# A601X.net
KiCad netlist of a schematic drawn in EAGLE
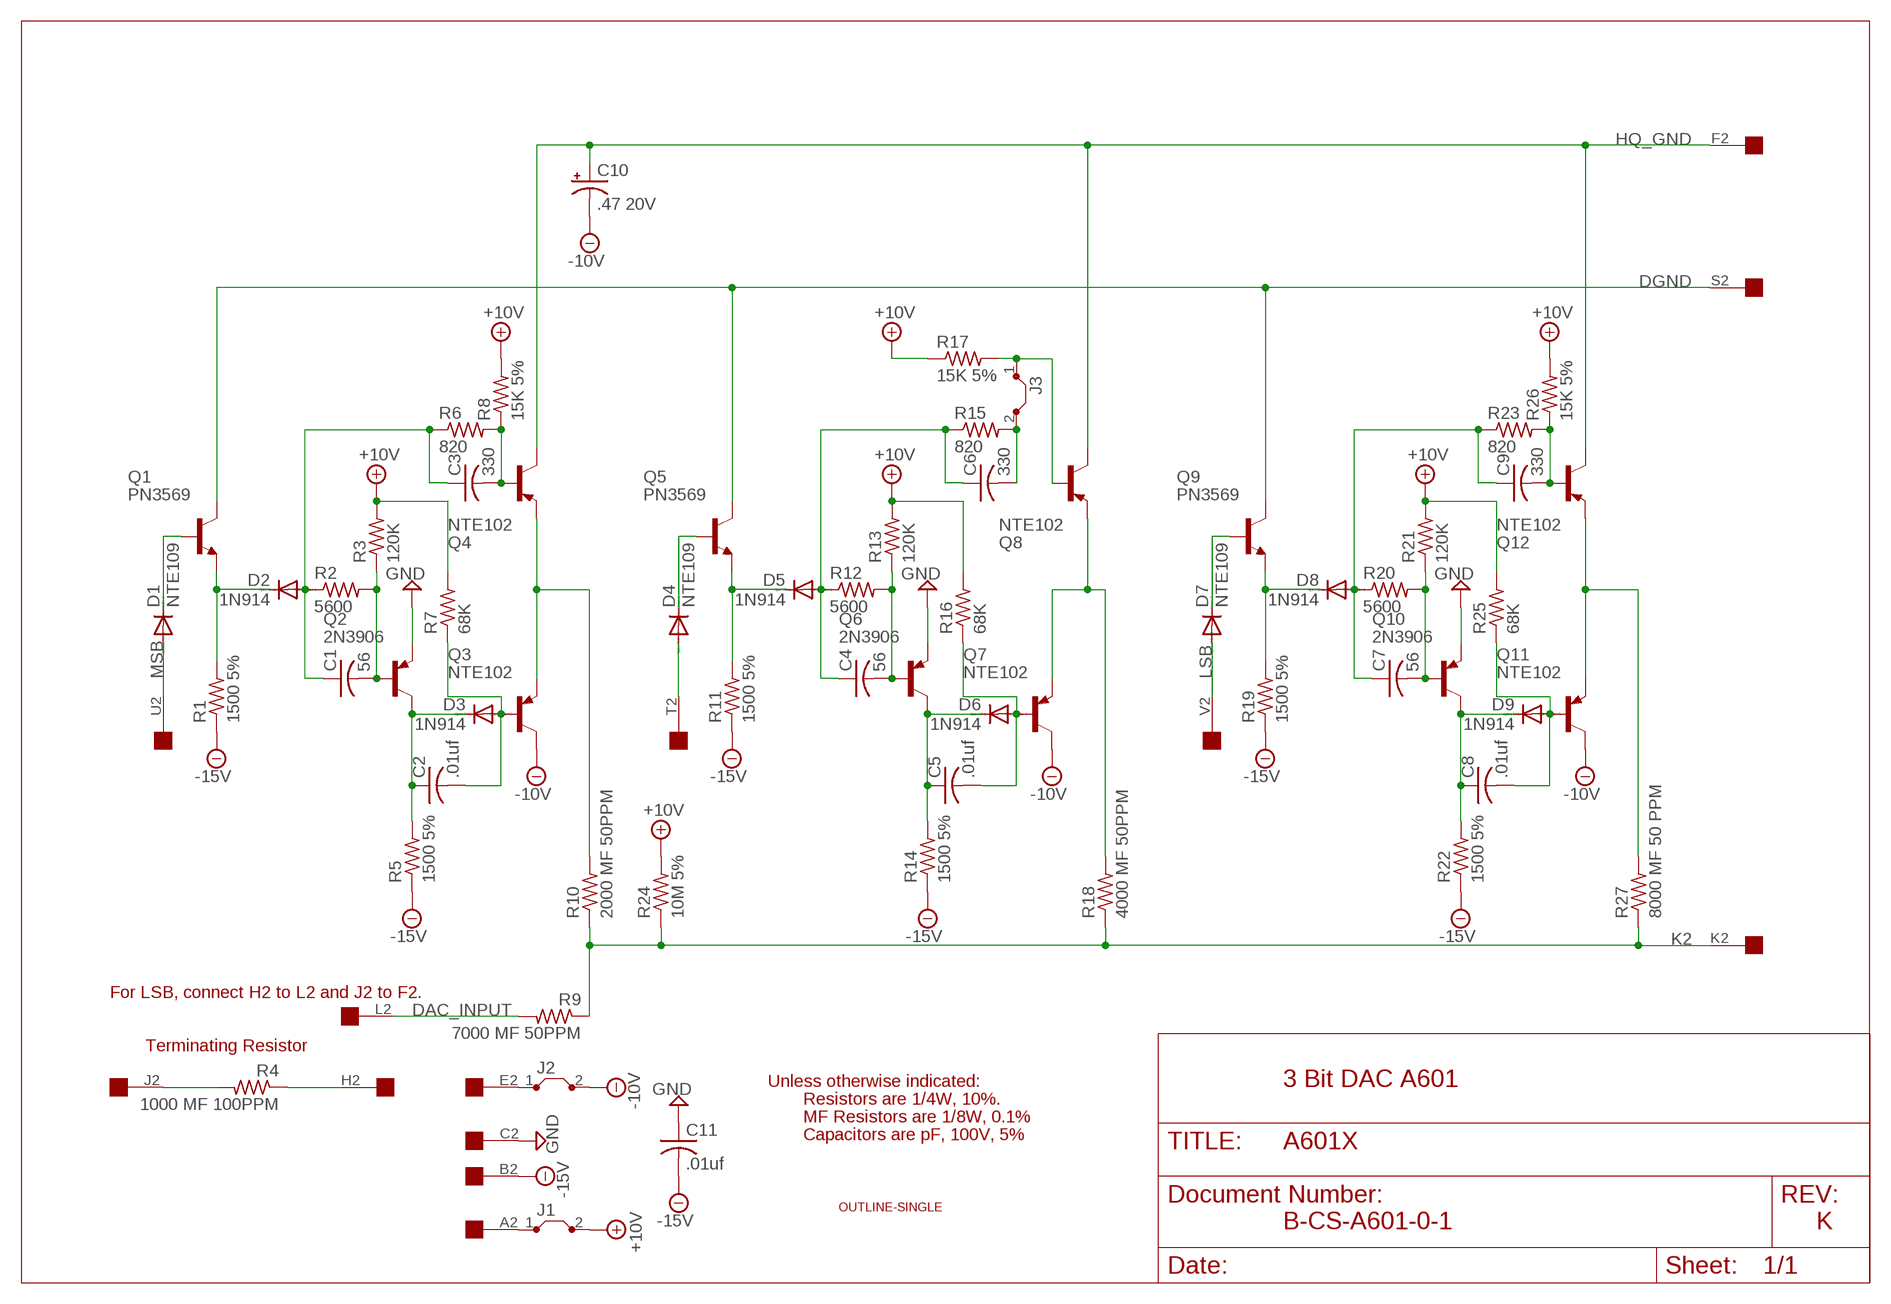
[diagram p0: schematic, sheet 1]

(export (version "E")
  (design (tool "Eeschema 10.0.6"))
  (components
    (comp (ref "C1")
      (value "56")
      (footprint "eagle-import:C075-032X103")
      (libsource (lib "eagle-import") (part "C-US075-032X103"))
    )
    (comp (ref "C2")
      (value ".01uf")
      (footprint "eagle-import:C050-025X075")
      (libsource (lib "eagle-import") (part "C-US050-025X075"))
    )
    (comp (ref "C3")
      (value "330")
      (footprint "eagle-import:C075-032X103")
      (libsource (lib "eagle-import") (part "C-US075-032X103"))
    )
    (comp (ref "C4")
      (value "56")
      (footprint "eagle-import:C075-032X103")
      (libsource (lib "eagle-import") (part "C-US075-032X103"))
    )
    (comp (ref "C5")
      (value ".01uf")
      (footprint "eagle-import:C050-025X075")
      (libsource (lib "eagle-import") (part "C-US050-025X075"))
    )
    (comp (ref "C6")
      (value "330")
      (footprint "eagle-import:C075-032X103")
      (libsource (lib "eagle-import") (part "C-US075-032X103"))
    )
    (comp (ref "C7")
      (value "56")
      (footprint "eagle-import:C075-032X103")
      (libsource (lib "eagle-import") (part "C-US075-032X103"))
    )
    (comp (ref "C8")
      (value ".01uf")
      (footprint "eagle-import:C050-025X075")
      (libsource (lib "eagle-import") (part "C-US050-025X075"))
    )
    (comp (ref "C9")
      (value "330")
      (footprint "eagle-import:C075-032X103")
      (libsource (lib "eagle-import") (part "C-US075-032X103"))
    )
    (comp (ref "C10")
      (value ".47 20V")
      (footprint "eagle-import:E22-6")
      (libsource (lib "eagle-import") (part "CPOL-USE22-6AXIAL"))
    )
    (comp (ref "C11")
      (value ".01uf")
      (footprint "eagle-import:C050-025X075")
      (libsource (lib "eagle-import") (part "C-US050-025X075"))
    )
    (comp (ref "D1")
      (value "NTE109")
      (footprint "eagle-import:DO35-10")
      (libsource (lib "eagle-import") (part "1N4148DO35-10"))
    )
    (comp (ref "D2")
      (value "1N914")
      (footprint "eagle-import:DO35-10")
      (libsource (lib "eagle-import") (part "1N4148DO35-10"))
    )
    (comp (ref "D3")
      (value "1N914")
      (footprint "eagle-import:DO35-10")
      (libsource (lib "eagle-import") (part "1N4148DO35-10"))
    )
    (comp (ref "D4")
      (value "NTE109")
      (footprint "eagle-import:DO35-10")
      (libsource (lib "eagle-import") (part "1N4148DO35-10"))
    )
    (comp (ref "D5")
      (value "1N914")
      (footprint "eagle-import:DO35-10")
      (libsource (lib "eagle-import") (part "1N4148DO35-10"))
    )
    (comp (ref "D6")
      (value "1N914")
      (footprint "eagle-import:DO35-10")
      (libsource (lib "eagle-import") (part "1N4148DO35-10"))
    )
    (comp (ref "D7")
      (value "NTE109")
      (footprint "eagle-import:DO35-10")
      (libsource (lib "eagle-import") (part "1N4148DO35-10"))
    )
    (comp (ref "D8")
      (value "1N914")
      (footprint "eagle-import:DO35-10")
      (libsource (lib "eagle-import") (part "1N4148DO35-10"))
    )
    (comp (ref "D9")
      (value "1N914")
      (footprint "eagle-import:DO35-10")
      (libsource (lib "eagle-import") (part "1N4148DO35-10"))
    )
    (comp (ref "J1")
      (value "J10MM")
      (footprint "eagle-import:10")
      (libsource (lib "eagle-import") (part "J10MM"))
    )
    (comp (ref "J2")
      (value "J10MM")
      (footprint "eagle-import:10")
      (libsource (lib "eagle-import") (part "J10MM"))
    )
    (comp (ref "J3")
      (value "J10MM")
      (footprint "eagle-import:10")
      (libsource (lib "eagle-import") (part "J10MM"))
    )
    (comp (ref "Q1")
      (value "PN3569")
      (footprint "eagle-import:TO39")
      (libsource (lib "eagle-import") (part "-NPN-TO39-EBC2N1613"))
    )
    (comp (ref "Q2")
      (value "2N3906")
      (footprint "eagle-import:TO39")
      (libsource (lib "eagle-import") (part "2N2904A"))
    )
    (comp (ref "Q3")
      (value "NTE102")
      (footprint "eagle-import:TO39")
      (libsource (lib "eagle-import") (part "2N2904A"))
    )
    (comp (ref "Q4")
      (value "NTE102")
      (footprint "eagle-import:TO39")
      (libsource (lib "eagle-import") (part "2N2904A"))
    )
    (comp (ref "Q5")
      (value "PN3569")
      (footprint "eagle-import:TO39")
      (libsource (lib "eagle-import") (part "-NPN-TO39-EBC2N1613"))
    )
    (comp (ref "Q6")
      (value "2N3906")
      (footprint "eagle-import:TO39")
      (libsource (lib "eagle-import") (part "2N2904A"))
    )
    (comp (ref "Q7")
      (value "NTE102")
      (footprint "eagle-import:TO39")
      (libsource (lib "eagle-import") (part "2N2904A"))
    )
    (comp (ref "Q8")
      (value "NTE102")
      (footprint "eagle-import:TO39")
      (libsource (lib "eagle-import") (part "2N2904A"))
    )
    (comp (ref "Q9")
      (value "PN3569")
      (footprint "eagle-import:TO39")
      (libsource (lib "eagle-import") (part "-NPN-TO39-EBC2N1613"))
    )
    (comp (ref "Q10")
      (value "2N3906")
      (footprint "eagle-import:TO39")
      (libsource (lib "eagle-import") (part "2N2904A"))
    )
    (comp (ref "Q11")
      (value "NTE102")
      (footprint "eagle-import:TO39")
      (libsource (lib "eagle-import") (part "2N2904A"))
    )
    (comp (ref "Q12")
      (value "NTE102")
      (footprint "eagle-import:TO39")
      (libsource (lib "eagle-import") (part "2N2904A"))
    )
    (comp (ref "R1")
      (value "1500 5%")
      (footprint "eagle-import:0207_10")
      (libsource (lib "eagle-import") (part "R-US_0207/10"))
    )
    (comp (ref "R2")
      (value "5600")
      (footprint "eagle-import:0207_10")
      (libsource (lib "eagle-import") (part "R-US_0207/10"))
    )
    (comp (ref "R3")
      (value "120K")
      (footprint "eagle-import:0207_10")
      (libsource (lib "eagle-import") (part "R-US_0207/10"))
    )
    (comp (ref "R4")
      (value "1000 MF 100PPM")
      (footprint "eagle-import:0309_12")
      (libsource (lib "eagle-import") (part "R-US_0309/12"))
    )
    (comp (ref "R5")
      (value "1500 5%")
      (footprint "eagle-import:0207_10")
      (libsource (lib "eagle-import") (part "R-US_0207/10"))
    )
    (comp (ref "R6")
      (value "820")
      (footprint "eagle-import:0207_10")
      (libsource (lib "eagle-import") (part "R-US_0207/10"))
    )
    (comp (ref "R7")
      (value "68K")
      (footprint "eagle-import:0207_10")
      (libsource (lib "eagle-import") (part "R-US_0207/10"))
    )
    (comp (ref "R8")
      (value "15K 5%")
      (footprint "eagle-import:0207_10")
      (libsource (lib "eagle-import") (part "R-US_0207/10"))
    )
    (comp (ref "R9")
      (value "7000 MF 50PPM")
      (footprint "eagle-import:0309_12")
      (libsource (lib "eagle-import") (part "R-US_0309/12"))
    )
    (comp (ref "R10")
      (value "2000 MF 50PPM")
      (footprint "eagle-import:0309_12")
      (libsource (lib "eagle-import") (part "R-US_0309/12"))
    )
    (comp (ref "R11")
      (value "1500 5%")
      (footprint "eagle-import:0207_10")
      (libsource (lib "eagle-import") (part "R-US_0207/10"))
    )
    (comp (ref "R12")
      (value "5600")
      (footprint "eagle-import:0207_10")
      (libsource (lib "eagle-import") (part "R-US_0207/10"))
    )
    (comp (ref "R13")
      (value "120K")
      (footprint "eagle-import:0207_10")
      (libsource (lib "eagle-import") (part "R-US_0207/10"))
    )
    (comp (ref "R14")
      (value "1500 5%")
      (footprint "eagle-import:0207_10")
      (libsource (lib "eagle-import") (part "R-US_0207/10"))
    )
    (comp (ref "R15")
      (value "820")
      (footprint "eagle-import:0207_10")
      (libsource (lib "eagle-import") (part "R-US_0207/10"))
    )
    (comp (ref "R16")
      (value "68K")
      (footprint "eagle-import:0207_10")
      (libsource (lib "eagle-import") (part "R-US_0207/10"))
    )
    (comp (ref "R17")
      (value "15K 5%")
      (footprint "eagle-import:0207_10")
      (libsource (lib "eagle-import") (part "R-US_0207/10"))
    )
    (comp (ref "R18")
      (value "4000 MF 50PPM")
      (footprint "eagle-import:0309_12")
      (libsource (lib "eagle-import") (part "R-US_0309/12"))
    )
    (comp (ref "R19")
      (value "1500 5%")
      (footprint "eagle-import:0207_10")
      (libsource (lib "eagle-import") (part "R-US_0207/10"))
    )
    (comp (ref "R20")
      (value "5600")
      (footprint "eagle-import:0207_10")
      (libsource (lib "eagle-import") (part "R-US_0207/10"))
    )
    (comp (ref "R21")
      (value "120K")
      (footprint "eagle-import:0207_10")
      (libsource (lib "eagle-import") (part "R-US_0207/10"))
    )
    (comp (ref "R22")
      (value "1500 5%")
      (footprint "eagle-import:0207_10")
      (libsource (lib "eagle-import") (part "R-US_0207/10"))
    )
    (comp (ref "R23")
      (value "820")
      (footprint "eagle-import:0207_10")
      (libsource (lib "eagle-import") (part "R-US_0207/10"))
    )
    (comp (ref "R24")
      (value "10M 5%")
      (footprint "eagle-import:0207_10")
      (libsource (lib "eagle-import") (part "R-US_0207/10"))
    )
    (comp (ref "R25")
      (value "68K")
      (footprint "eagle-import:0207_10")
      (libsource (lib "eagle-import") (part "R-US_0207/10"))
    )
    (comp (ref "R26")
      (value "15K 5%")
      (footprint "eagle-import:0207_10")
      (libsource (lib "eagle-import") (part "R-US_0207/10"))
    )
    (comp (ref "R27")
      (value "8000 MF 50 PPM")
      (footprint "eagle-import:0309_12")
      (libsource (lib "eagle-import") (part "R-US_0309/12"))
    )
    (comp (ref "U$1")
      (value "OUTLINE-SINGLE")
      (footprint "eagle-import:SINGLE")
      (libsource (lib "eagle-import") (part "OUTLINE-SINGLE"))
    )
    (comp (ref "U$3")
      (value "EDGE-1")
      (footprint "eagle-import:EDGE-CON1")
      (libsource (lib "eagle-import") (part "EDGE-1"))
    )
  )
  (nets
    (net (code "1") (name "+10V") (class "Default")
      (node (ref "J1") (pin "2") (pinfunction "2_2") (pintype "passive"))
      (node (ref "R13") (pin "2") (pinfunction "2_2") (pintype "passive"))
      (node (ref "R16") (pin "2") (pinfunction "2_2") (pintype "passive"))
      (node (ref "R17") (pin "1") (pinfunction "1_1") (pintype "passive"))
      (node (ref "R21") (pin "2") (pinfunction "2_2") (pintype "passive"))
      (node (ref "R24") (pin "2") (pinfunction "2_2") (pintype "passive"))
      (node (ref "R25") (pin "2") (pinfunction "2_2") (pintype "passive"))
      (node (ref "R26") (pin "2") (pinfunction "2_2") (pintype "passive"))
      (node (ref "R3") (pin "2") (pinfunction "2_2") (pintype "passive"))
      (node (ref "R7") (pin "2") (pinfunction "2_2") (pintype "passive"))
      (node (ref "R8") (pin "2") (pinfunction "2_2") (pintype "passive"))
    )
    (net (code "2") (name "-10V") (class "Default")
      (node (ref "C10") (pin "-") (pinfunction "-_-") (pintype "passive"))
      (node (ref "J2") (pin "2") (pinfunction "2_2") (pintype "passive"))
      (node (ref "Q11") (pin "3") (pinfunction "C_3") (pintype "passive"))
      (node (ref "Q3") (pin "3") (pinfunction "C_3") (pintype "passive"))
      (node (ref "Q7") (pin "3") (pinfunction "C_3") (pintype "passive"))
    )
    (net (code "3") (name "-15V") (class "Default")
      (node (ref "C11") (pin "2") (pinfunction "2_2") (pintype "passive"))
      (node (ref "R1") (pin "1") (pinfunction "1_1") (pintype "passive"))
      (node (ref "R11") (pin "1") (pinfunction "1_1") (pintype "passive"))
      (node (ref "R14") (pin "1") (pinfunction "1_1") (pintype "passive"))
      (node (ref "R19") (pin "1") (pinfunction "1_1") (pintype "passive"))
      (node (ref "R22") (pin "1") (pinfunction "1_1") (pintype "passive"))
      (node (ref "R5") (pin "1") (pinfunction "1_1") (pintype "passive"))
      (node (ref "U$3") (pin "B2") (pinfunction "1_B2") (pintype "bidirectional"))
    )
    (net (code "4") (name "/DAC_INPUT") (class "Default")
      (node (ref "R9") (pin "2") (pinfunction "2_2") (pintype "passive"))
      (node (ref "U$3") (pin "L2") (pinfunction "1_L2") (pintype "bidirectional"))
    )
    (net (code "5") (name "/DGND") (class "Default")
      (node (ref "Q1") (pin "3") (pinfunction "C_3") (pintype "passive"))
      (node (ref "Q5") (pin "3") (pinfunction "C_3") (pintype "passive"))
      (node (ref "Q9") (pin "3") (pinfunction "C_3") (pintype "passive"))
      (node (ref "U$3") (pin "S2") (pinfunction "1_S2") (pintype "bidirectional"))
    )
    (net (code "6") (name "/HQ_GND") (class "Default")
      (node (ref "C10") (pin "+") (pinfunction "+_+") (pintype "passive"))
      (node (ref "Q12") (pin "3") (pinfunction "C_3") (pintype "passive"))
      (node (ref "Q4") (pin "3") (pinfunction "C_3") (pintype "passive"))
      (node (ref "Q8") (pin "3") (pinfunction "C_3") (pintype "passive"))
      (node (ref "U$3") (pin "F2") (pinfunction "1_F2") (pintype "bidirectional"))
    )
    (net (code "7") (name "/K2") (class "Default")
      (node (ref "R10") (pin "1") (pinfunction "1_1") (pintype "passive"))
      (node (ref "R18") (pin "1") (pinfunction "1_1") (pintype "passive"))
      (node (ref "R24") (pin "1") (pinfunction "1_1") (pintype "passive"))
      (node (ref "R27") (pin "1") (pinfunction "1_1") (pintype "passive"))
      (node (ref "R9") (pin "1") (pinfunction "1_1") (pintype "passive"))
      (node (ref "U$3") (pin "K2") (pinfunction "1_K2") (pintype "bidirectional"))
    )
    (net (code "8") (name "/LSB") (class "Default")
      (node (ref "D7") (pin "A") (pinfunction "A_A") (pintype "passive"))
      (node (ref "U$3") (pin "V2") (pinfunction "1_V2") (pintype "bidirectional"))
    )
    (net (code "9") (name "/MSB") (class "Default")
      (node (ref "D1") (pin "A") (pinfunction "A_A") (pintype "passive"))
      (node (ref "U$3") (pin "U2") (pinfunction "1_U2") (pintype "bidirectional"))
    )
    (net (code "10") (name "GND") (class "Default")
      (node (ref "C11") (pin "1") (pinfunction "1_1") (pintype "passive"))
      (node (ref "Q10") (pin "1") (pinfunction "E_1") (pintype "passive"))
      (node (ref "Q2") (pin "1") (pinfunction "E_1") (pintype "passive"))
      (node (ref "Q6") (pin "1") (pinfunction "E_1") (pintype "passive"))
      (node (ref "U$3") (pin "C2") (pinfunction "1_C2") (pintype "bidirectional"))
    )
    (net (code "11") (name "Net-(C1-Pad1)") (class "Default")
      (node (ref "C1") (pin "1") (pinfunction "1_1") (pintype "passive"))
      (node (ref "C3") (pin "1") (pinfunction "1_1") (pintype "passive"))
      (node (ref "D2") (pin "A") (pinfunction "A_A") (pintype "passive"))
      (node (ref "R2") (pin "1") (pinfunction "1_1") (pintype "passive"))
      (node (ref "R6") (pin "1") (pinfunction "1_1") (pintype "passive"))
    )
    (net (code "12") (name "Net-(C4-Pad1)") (class "Default")
      (node (ref "C4") (pin "1") (pinfunction "1_1") (pintype "passive"))
      (node (ref "C6") (pin "1") (pinfunction "1_1") (pintype "passive"))
      (node (ref "D5") (pin "A") (pinfunction "A_A") (pintype "passive"))
      (node (ref "R12") (pin "1") (pinfunction "1_1") (pintype "passive"))
      (node (ref "R15") (pin "1") (pinfunction "1_1") (pintype "passive"))
    )
    (net (code "13") (name "Net-(C6-Pad2)") (class "Default")
      (node (ref "C6") (pin "2") (pinfunction "2_2") (pintype "passive"))
      (node (ref "J3") (pin "2") (pinfunction "2_2") (pintype "passive"))
      (node (ref "R15") (pin "2") (pinfunction "2_2") (pintype "passive"))
    )
    (net (code "14") (name "Net-(C7-Pad1)") (class "Default")
      (node (ref "C7") (pin "1") (pinfunction "1_1") (pintype "passive"))
      (node (ref "C9") (pin "1") (pinfunction "1_1") (pintype "passive"))
      (node (ref "D8") (pin "A") (pinfunction "A_A") (pintype "passive"))
      (node (ref "R20") (pin "1") (pinfunction "1_1") (pintype "passive"))
      (node (ref "R23") (pin "1") (pinfunction "1_1") (pintype "passive"))
    )
    (net (code "15") (name "Net-(Q1-B)") (class "Default")
      (node (ref "D1") (pin "C") (pinfunction "C_C") (pintype "passive"))
      (node (ref "Q1") (pin "2") (pinfunction "B_2") (pintype "passive"))
    )
    (net (code "16") (name "Net-(Q1-E)") (class "Default")
      (node (ref "D2") (pin "C") (pinfunction "C_C") (pintype "passive"))
      (node (ref "Q1") (pin "1") (pinfunction "E_1") (pintype "passive"))
      (node (ref "R1") (pin "2") (pinfunction "2_2") (pintype "passive"))
    )
    (net (code "17") (name "Net-(Q2-B)") (class "Default")
      (node (ref "C1") (pin "2") (pinfunction "2_2") (pintype "passive"))
      (node (ref "Q2") (pin "2") (pinfunction "B_2") (pintype "passive"))
      (node (ref "R2") (pin "2") (pinfunction "2_2") (pintype "passive"))
      (node (ref "R3") (pin "1") (pinfunction "1_1") (pintype "passive"))
    )
    (net (code "18") (name "Net-(Q2-C)") (class "Default")
      (node (ref "C2") (pin "1") (pinfunction "1_1") (pintype "passive"))
      (node (ref "D3") (pin "C") (pinfunction "C_C") (pintype "passive"))
      (node (ref "Q2") (pin "3") (pinfunction "C_3") (pintype "passive"))
      (node (ref "R5") (pin "2") (pinfunction "2_2") (pintype "passive"))
    )
    (net (code "19") (name "Net-(Q3-B)") (class "Default")
      (node (ref "C2") (pin "2") (pinfunction "2_2") (pintype "passive"))
      (node (ref "D3") (pin "A") (pinfunction "A_A") (pintype "passive"))
      (node (ref "Q3") (pin "2") (pinfunction "B_2") (pintype "passive"))
      (node (ref "R7") (pin "1") (pinfunction "1_1") (pintype "passive"))
    )
    (net (code "20") (name "Net-(Q3-E)") (class "Default")
      (node (ref "Q3") (pin "1") (pinfunction "E_1") (pintype "passive"))
      (node (ref "Q4") (pin "1") (pinfunction "E_1") (pintype "passive"))
      (node (ref "R10") (pin "2") (pinfunction "2_2") (pintype "passive"))
    )
    (net (code "21") (name "Net-(Q4-B)") (class "Default")
      (node (ref "C3") (pin "2") (pinfunction "2_2") (pintype "passive"))
      (node (ref "Q4") (pin "2") (pinfunction "B_2") (pintype "passive"))
      (node (ref "R6") (pin "2") (pinfunction "2_2") (pintype "passive"))
      (node (ref "R8") (pin "1") (pinfunction "1_1") (pintype "passive"))
    )
    (net (code "22") (name "Net-(Q5-B)") (class "Default")
      (node (ref "D4") (pin "C") (pinfunction "C_C") (pintype "passive"))
      (node (ref "Q5") (pin "2") (pinfunction "B_2") (pintype "passive"))
    )
    (net (code "23") (name "Net-(Q5-E)") (class "Default")
      (node (ref "D5") (pin "C") (pinfunction "C_C") (pintype "passive"))
      (node (ref "Q5") (pin "1") (pinfunction "E_1") (pintype "passive"))
      (node (ref "R11") (pin "2") (pinfunction "2_2") (pintype "passive"))
    )
    (net (code "24") (name "Net-(Q6-B)") (class "Default")
      (node (ref "C4") (pin "2") (pinfunction "2_2") (pintype "passive"))
      (node (ref "Q6") (pin "2") (pinfunction "B_2") (pintype "passive"))
      (node (ref "R12") (pin "2") (pinfunction "2_2") (pintype "passive"))
      (node (ref "R13") (pin "1") (pinfunction "1_1") (pintype "passive"))
    )
    (net (code "25") (name "Net-(Q6-C)") (class "Default")
      (node (ref "C5") (pin "1") (pinfunction "1_1") (pintype "passive"))
      (node (ref "D6") (pin "C") (pinfunction "C_C") (pintype "passive"))
      (node (ref "Q6") (pin "3") (pinfunction "C_3") (pintype "passive"))
      (node (ref "R14") (pin "2") (pinfunction "2_2") (pintype "passive"))
    )
    (net (code "26") (name "Net-(Q7-B)") (class "Default")
      (node (ref "C5") (pin "2") (pinfunction "2_2") (pintype "passive"))
      (node (ref "D6") (pin "A") (pinfunction "A_A") (pintype "passive"))
      (node (ref "Q7") (pin "2") (pinfunction "B_2") (pintype "passive"))
      (node (ref "R16") (pin "1") (pinfunction "1_1") (pintype "passive"))
    )
    (net (code "27") (name "Net-(Q7-E)") (class "Default")
      (node (ref "Q7") (pin "1") (pinfunction "E_1") (pintype "passive"))
      (node (ref "Q8") (pin "1") (pinfunction "E_1") (pintype "passive"))
      (node (ref "R18") (pin "2") (pinfunction "2_2") (pintype "passive"))
    )
    (net (code "28") (name "Net-(Q8-B)") (class "Default")
      (node (ref "J3") (pin "1") (pinfunction "1_1") (pintype "passive"))
      (node (ref "Q8") (pin "2") (pinfunction "B_2") (pintype "passive"))
      (node (ref "R17") (pin "2") (pinfunction "2_2") (pintype "passive"))
    )
    (net (code "29") (name "Net-(Q9-B)") (class "Default")
      (node (ref "D7") (pin "C") (pinfunction "C_C") (pintype "passive"))
      (node (ref "Q9") (pin "2") (pinfunction "B_2") (pintype "passive"))
    )
    (net (code "30") (name "Net-(Q9-E)") (class "Default")
      (node (ref "D8") (pin "C") (pinfunction "C_C") (pintype "passive"))
      (node (ref "Q9") (pin "1") (pinfunction "E_1") (pintype "passive"))
      (node (ref "R19") (pin "2") (pinfunction "2_2") (pintype "passive"))
    )
    (net (code "31") (name "Net-(Q10-B)") (class "Default")
      (node (ref "C7") (pin "2") (pinfunction "2_2") (pintype "passive"))
      (node (ref "Q10") (pin "2") (pinfunction "B_2") (pintype "passive"))
      (node (ref "R20") (pin "2") (pinfunction "2_2") (pintype "passive"))
      (node (ref "R21") (pin "1") (pinfunction "1_1") (pintype "passive"))
    )
    (net (code "32") (name "Net-(Q10-C)") (class "Default")
      (node (ref "C8") (pin "1") (pinfunction "1_1") (pintype "passive"))
      (node (ref "D9") (pin "C") (pinfunction "C_C") (pintype "passive"))
      (node (ref "Q10") (pin "3") (pinfunction "C_3") (pintype "passive"))
      (node (ref "R22") (pin "2") (pinfunction "2_2") (pintype "passive"))
    )
    (net (code "33") (name "Net-(Q11-B)") (class "Default")
      (node (ref "C8") (pin "2") (pinfunction "2_2") (pintype "passive"))
      (node (ref "D9") (pin "A") (pinfunction "A_A") (pintype "passive"))
      (node (ref "Q11") (pin "2") (pinfunction "B_2") (pintype "passive"))
      (node (ref "R25") (pin "1") (pinfunction "1_1") (pintype "passive"))
    )
    (net (code "34") (name "Net-(Q11-E)") (class "Default")
      (node (ref "Q11") (pin "1") (pinfunction "E_1") (pintype "passive"))
      (node (ref "Q12") (pin "1") (pinfunction "E_1") (pintype "passive"))
      (node (ref "R27") (pin "2") (pinfunction "2_2") (pintype "passive"))
    )
    (net (code "35") (name "Net-(Q12-B)") (class "Default")
      (node (ref "C9") (pin "2") (pinfunction "2_2") (pintype "passive"))
      (node (ref "Q12") (pin "2") (pinfunction "B_2") (pintype "passive"))
      (node (ref "R23") (pin "2") (pinfunction "2_2") (pintype "passive"))
      (node (ref "R26") (pin "1") (pinfunction "1_1") (pintype "passive"))
    )
    (net (code "36") (name "Net-(U$3A-1)") (class "Default")
      (node (ref "J1") (pin "1") (pinfunction "1_1") (pintype "passive"))
      (node (ref "U$3") (pin "A2") (pinfunction "1_A2") (pintype "bidirectional"))
    )
    (net (code "37") (name "Net-(U$3E-1)") (class "Default")
      (node (ref "J2") (pin "1") (pinfunction "1_1") (pintype "passive"))
      (node (ref "U$3") (pin "E2") (pinfunction "1_E2") (pintype "bidirectional"))
    )
    (net (code "38") (name "Net-(U$3G-1)") (class "Default")
      (node (ref "R4") (pin "1") (pinfunction "1_1") (pintype "passive"))
      (node (ref "U$3") (pin "H2") (pinfunction "1_H2") (pintype "bidirectional"))
    )
    (net (code "39") (name "Net-(U$3H-1)") (class "Default")
      (node (ref "R4") (pin "2") (pinfunction "2_2") (pintype "passive"))
      (node (ref "U$3") (pin "J2") (pinfunction "1_J2") (pintype "bidirectional"))
    )
    (net (code "40") (name "Net-(U$3P-1)") (class "Default")
      (node (ref "D4") (pin "A") (pinfunction "A_A") (pintype "passive"))
      (node (ref "U$3") (pin "T2") (pinfunction "1_T2") (pintype "bidirectional"))
    )
  )
)
